# magic_1_0v.net
KiCad netlist of a schematic drawn in EAGLE
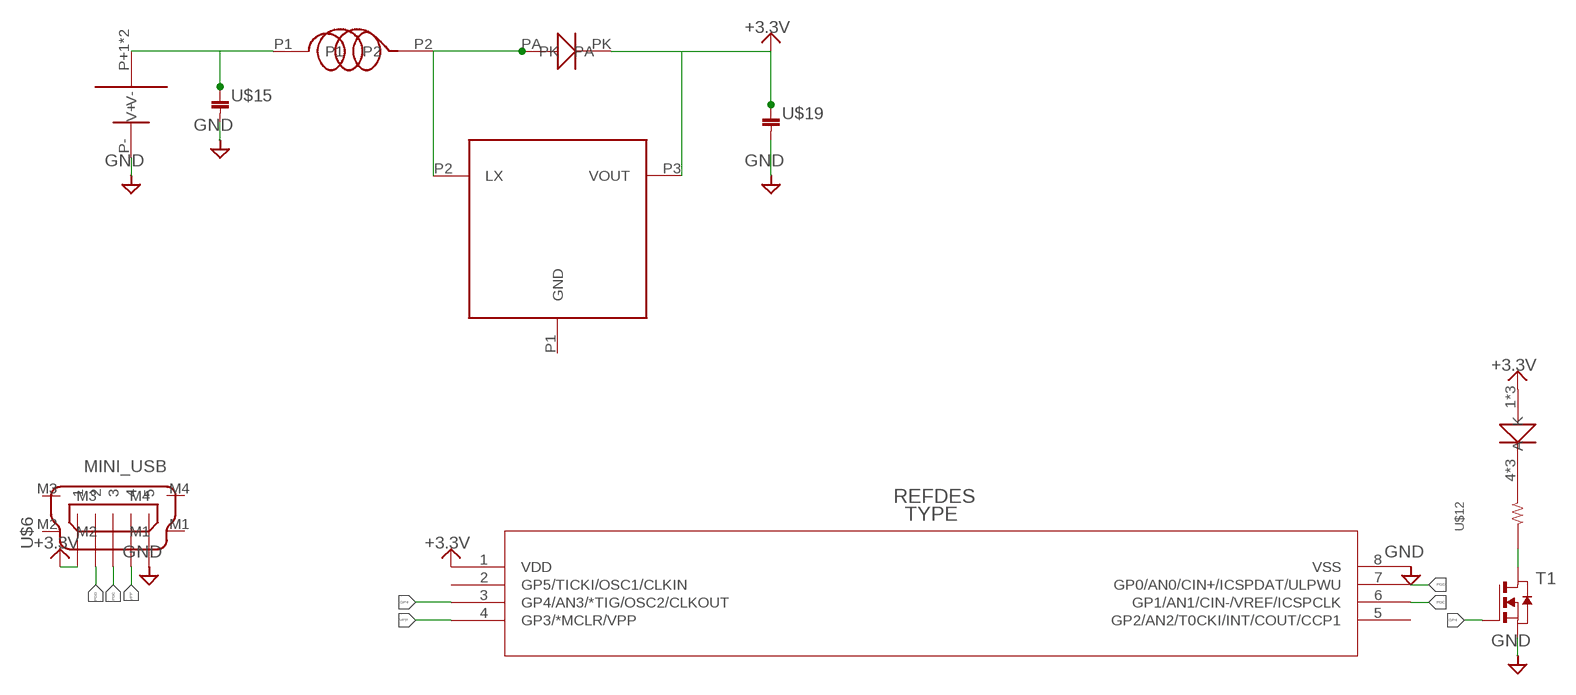
[diagram p0: schematic, sheet 1]

(export (version "E")
  (design (tool "Eeschema 10.0.6"))
  (components
    (comp (ref "T1")
      (value "NMOSSOT23")
      (footprint "eagle-import:SOT-23")
      (libsource (lib "eagle-import") (part "NMOSSOT23"))
    )
    (comp (ref "U$1")
      (value "PIC12F683-X/SN")
      (footprint "eagle-import:SOIC8-N_MC")
      (libsource (lib "eagle-import") (part "PIC12F683-X/SN"))
    )
    (comp (ref "U$2")
      (value "CR2032")
      (footprint "eagle-import:SMTM2032")
      (libsource (lib "eagle-import") (part "CR2032"))
    )
    (comp (ref "U$6")
      (value "MINI_USB")
      (footprint "eagle-import:MINI_USB")
      (libsource (lib "eagle-import") (part "MINI_USB"))
    )
    (comp (ref "U$9")
      (value "OSB64")
      (footprint "eagle-import:ＯＳＢ６４")
      (libsource (lib "eagle-import") (part "OSB64"))
    )
    (comp (ref "U$12")
      (value "RESISTOR__SMD")
      (footprint "eagle-import:1608")
      (libsource (lib "eagle-import") (part "RESISTOR__SMD"))
    )
    (comp (ref "U$13")
      (value "NPI16W")
      (footprint "eagle-import:NPI16W")
      (libsource (lib "eagle-import") (part "NPI16W"))
    )
    (comp (ref "U$14")
      (value "HT7733")
      (footprint "eagle-import:SOT23")
      (libsource (lib "eagle-import") (part "HT7733"))
    )
    (comp (ref "U$15")
      (value "3225")
      (footprint "eagle-import:3225")
      (libsource (lib "eagle-import") (part "3225"))
    )
    (comp (ref "U$17")
      (value "RSX101")
      (footprint "eagle-import:TUMD2")
      (libsource (lib "eagle-import") (part "RSX101"))
    )
    (comp (ref "U$19")
      (value "2012")
      (footprint "eagle-import:2012")
      (libsource (lib "eagle-import") (part "2012"))
    )
  )
  (nets
    (net (code "1") (name "+3.3V") (class "Default")
      (node (ref "U$1") (pin "1") (pinfunction "VDD_1") (pintype "passive"))
      (node (ref "U$14") (pin "P3") (pinfunction "VOUT_P3") (pintype "bidirectional"))
      (node (ref "U$17") (pin "PK") (pinfunction "PK_PK") (pintype "bidirectional"))
      (node (ref "U$19") (pin "1") (pinfunction "1_1") (pintype "passive"))
      (node (ref "U$6") (pin "1") (pinfunction "1_1") (pintype "input"))
      (node (ref "U$9") (pin "1") (pinfunction "A_1") (pintype "bidirectional"))
      (node (ref "U$9") (pin "2") (pinfunction "A_2") (pintype "bidirectional"))
      (node (ref "U$9") (pin "3") (pinfunction "A_3") (pintype "bidirectional"))
    )
    (net (code "2") (name "GND") (class "Default")
      (node (ref "T1") (pin "2") (pinfunction "S_2") (pintype "passive"))
      (node (ref "U$1") (pin "8") (pinfunction "VSS_8") (pintype "passive"))
      (node (ref "U$15") (pin "P$2") (pinfunction "2_P$2") (pintype "passive"))
      (node (ref "U$19") (pin "2") (pinfunction "2_2") (pintype "passive"))
      (node (ref "U$2") (pin "P-") (pinfunction "V-_P-") (pintype "bidirectional"))
      (node (ref "U$6") (pin "5") (pinfunction "5_5") (pintype "input"))
    )
    (net (code "3") (name "GP4") (class "Default")
      (node (ref "T1") (pin "3") (pinfunction "G_3") (pintype "passive"))
      (node (ref "U$1") (pin "3") (pinfunction "GP4/AN3/*TIG/OSC2/CLKOUT_3") (pintype "passive"))
    )
    (net (code "4") (name "Net-(T1-D)") (class "Default")
      (node (ref "T1") (pin "1") (pinfunction "D_1") (pintype "passive"))
      (node (ref "U$12") (pin "1") (pinfunction "P$1_1") (pintype "passive"))
    )
    (net (code "5") (name "Net-(U$12-P$2)") (class "Default")
      (node (ref "U$12") (pin "2") (pinfunction "P$2_2") (pintype "passive"))
      (node (ref "U$9") (pin "4") (pinfunction "K_4") (pintype "bidirectional"))
      (node (ref "U$9") (pin "5") (pinfunction "K_5") (pintype "bidirectional"))
      (node (ref "U$9") (pin "6") (pinfunction "K_6") (pintype "bidirectional"))
    )
    (net (code "6") (name "Net-(U$14-LX)") (class "Default")
      (node (ref "U$13") (pin "P2") (pinfunction "P2_P2") (pintype "bidirectional"))
      (node (ref "U$14") (pin "P2") (pinfunction "LX_P2") (pintype "bidirectional"))
      (node (ref "U$17") (pin "PA") (pinfunction "PA_PA") (pintype "bidirectional"))
    )
    (net (code "7") (name "Net-(U$15-1)") (class "Default")
      (node (ref "U$13") (pin "P1") (pinfunction "P1_P1") (pintype "bidirectional"))
      (node (ref "U$15") (pin "P$1") (pinfunction "1_P$1") (pintype "passive"))
      (node (ref "U$2") (pin "P+1") (pinfunction "V+_P+1") (pintype "bidirectional"))
      (node (ref "U$2") (pin "P+2") (pinfunction "V+_P+2") (pintype "bidirectional"))
    )
    (net (code "8") (name "PGC") (class "Default")
      (node (ref "U$1") (pin "6") (pinfunction "GP1/AN1/CIN-/VREF/ICSPCLK_6") (pintype "passive"))
      (node (ref "U$6") (pin "3") (pinfunction "3_3") (pintype "input"))
    )
    (net (code "9") (name "PGD") (class "Default")
      (node (ref "U$1") (pin "7") (pinfunction "GP0/AN0/CIN+/ICSPDAT/ULPWU_7") (pintype "passive"))
      (node (ref "U$6") (pin "2") (pinfunction "2_2") (pintype "input"))
    )
    (net (code "10") (name "VPP") (class "Default")
      (node (ref "U$1") (pin "4") (pinfunction "GP3/*MCLR/VPP_4") (pintype "passive"))
      (node (ref "U$6") (pin "4") (pinfunction "4_4") (pintype "input"))
    )
    (net (code "11") (name "unconnected-(U$1-GP2{slash}AN2{slash}T0CKI{slash}INT{slash}COUT{slash}CCP1-Pad5)") (class "Default")
      (node (ref "U$1") (pin "5") (pinfunction "GP2/AN2/T0CKI/INT/COUT/CCP1_5") (pintype "passive"))
    )
    (net (code "12") (name "unconnected-(U$1-GP5{slash}TICKI{slash}OSC1{slash}CLKIN-Pad2)") (class "Default")
      (node (ref "U$1") (pin "2") (pinfunction "GP5/TICKI/OSC1/CLKIN_2") (pintype "passive"))
    )
    (net (code "13") (name "unconnected-(U$6-PadM1)") (class "Default")
      (node (ref "U$6") (pin "M1") (pinfunction "M1_M1") (pintype "bidirectional"))
    )
    (net (code "14") (name "unconnected-(U$6-PadM2)") (class "Default")
      (node (ref "U$6") (pin "M2") (pinfunction "M2_M2") (pintype "bidirectional"))
    )
    (net (code "15") (name "unconnected-(U$6-PadM3)") (class "Default")
      (node (ref "U$6") (pin "M3") (pinfunction "M3_M3") (pintype "bidirectional"))
    )
    (net (code "16") (name "unconnected-(U$6-PadM4)") (class "Default")
      (node (ref "U$6") (pin "M4") (pinfunction "M4_M4") (pintype "bidirectional"))
    )
    (net (code "17") (name "unconnected-(U$14-GND-PadP1)") (class "Default")
      (node (ref "U$14") (pin "P1") (pinfunction "GND_P1") (pintype "bidirectional"))
    )
  )
)
